# kurskTovideroRaspi.net
KiCad netlist of a schematic drawn in EAGLE
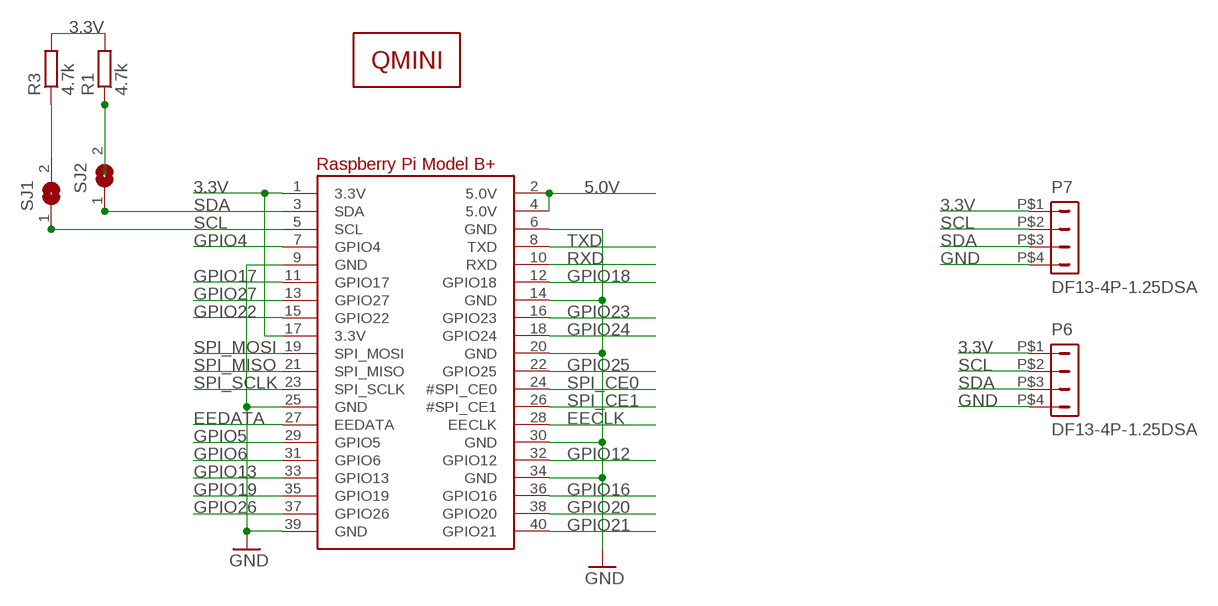
[diagram p0: schematic, sheet 1]
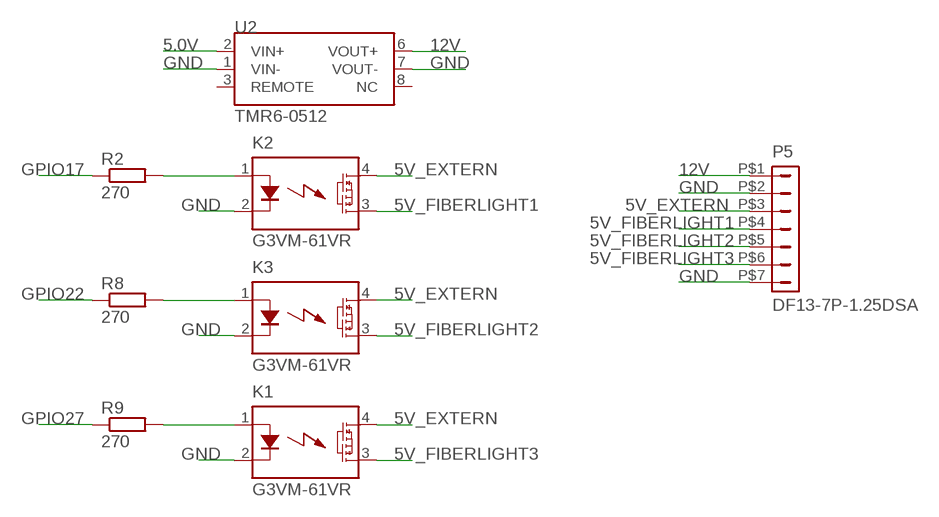
[diagram p1: schematic, sheet 2]
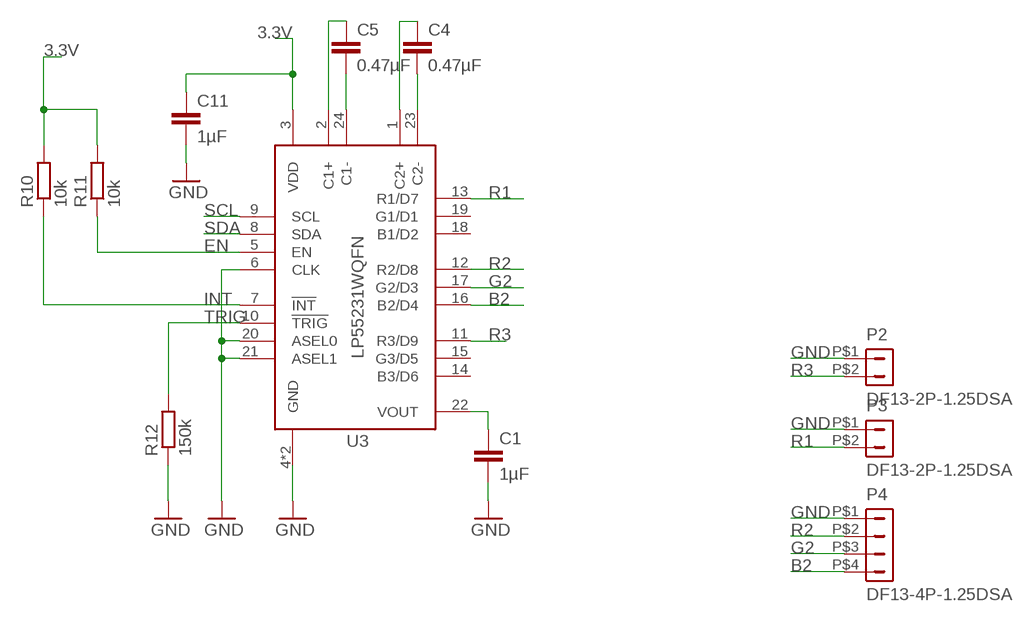
[diagram p2: schematic, sheet 3]
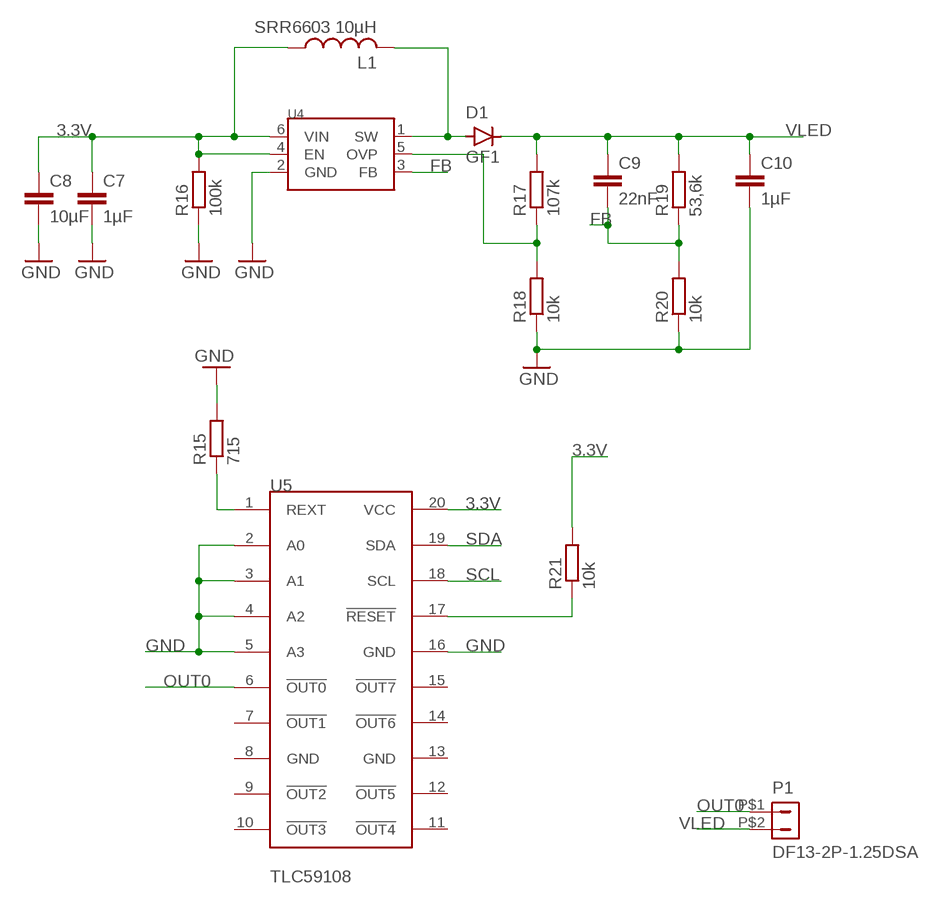
[diagram p3: schematic, sheet 4]

(export (version "E")
  (design (tool "Eeschema 10.0.6"))
  (components
    (comp (ref "K1")
      (value "G3VM-61VR")
      (footprint "eagle-import:SOP04")
      (description "NO DESCRIPTION")
      (fields
        (field (name "MANUFACTURER") "UNKNOWN MANUFACTURER")
        (field (name "MANUFACTURERPARTNUMBER") "UNKNOWN MANUFACTURER PART NUMBER")
        (field (name "MF") "OMRON")
        (field (name "MPN") "G3VM-61VR(TR05)")
        (field (name "OC_FARNELL") "2889501")
      )
      (libsource (lib "eagle-import") (part "AQYSOP22"))
    )
    (comp (ref "K2")
      (value "G3VM-61VR")
      (footprint "eagle-import:SOP04")
      (description "NO DESCRIPTION")
      (fields
        (field (name "MANUFACTURER") "UNKNOWN MANUFACTURER")
        (field (name "MANUFACTURERPARTNUMBER") "UNKNOWN MANUFACTURER PART NUMBER")
        (field (name "MF") "OMRON")
        (field (name "MPN") "G3VM-61VR(TR05)")
        (field (name "OC_FARNELL") "2889501")
      )
      (libsource (lib "eagle-import") (part "AQYSOP22"))
    )
    (comp (ref "K3")
      (value "G3VM-61VR")
      (footprint "eagle-import:SOP04")
      (description "NO DESCRIPTION")
      (fields
        (field (name "MANUFACTURER") "UNKNOWN MANUFACTURER")
        (field (name "MANUFACTURERPARTNUMBER") "UNKNOWN MANUFACTURER PART NUMBER")
        (field (name "MF") "OMRON")
        (field (name "MPN") "G3VM-61VR(TR05)")
        (field (name "OC_FARNELL") "2889501")
      )
      (libsource (lib "eagle-import") (part "AQYSOP22"))
    )
    (comp (ref "P5")
      (value "DF13-7P-1.25DSA")
      (footprint "eagle-import:DF13-7P-1.25DSA")
      (description "NO DESCRIPTION")
      (fields
        (field (name "MANUFACTURER") "UNKNOWN MANUFACTURER")
        (field (name "MANUFACTURERPARTNUMBER") "UNKNOWN MANUFACTURER PART NUMBER")
      )
      (libsource (lib "eagle-import") (part "DF13-7P-1.25DSA"))
    )
    (comp (ref "R2")
      (value "270")
      (footprint "eagle-import:R0805")
      (description "NO DESCRIPTION")
      (fields
        (field (name "MANUFACTURER") "UNKNOWN MANUFACTURER")
        (field (name "MANUFACTURERPARTNUMBER") "UNKNOWN MANUFACTURER PART NUMBER")
      )
      (libsource (lib "eagle-import") (part "R-EU_R0805"))
    )
    (comp (ref "R8")
      (value "270")
      (footprint "eagle-import:R0805")
      (description "NO DESCRIPTION")
      (fields
        (field (name "MANUFACTURER") "UNKNOWN MANUFACTURER")
        (field (name "MANUFACTURERPARTNUMBER") "UNKNOWN MANUFACTURER PART NUMBER")
      )
      (libsource (lib "eagle-import") (part "R-EU_R0805"))
    )
    (comp (ref "R9")
      (value "270")
      (footprint "eagle-import:R0805")
      (description "NO DESCRIPTION")
      (fields
        (field (name "MANUFACTURER") "UNKNOWN MANUFACTURER")
        (field (name "MANUFACTURERPARTNUMBER") "UNKNOWN MANUFACTURER PART NUMBER")
      )
      (libsource (lib "eagle-import") (part "R-EU_R0805"))
    )
    (comp (ref "U2")
      (value "TMR6-0512")
      (footprint "eagle-import:TMR6-0512")
      (description "NO DESCRIPTION")
      (fields
        (field (name "MANUFACTURER") "UNKNOWN MANUFACTURER")
        (field (name "MANUFACTURERPARTNUMBER") "UNKNOWN MANUFACTURER PART NUMBER")
      )
      (libsource (lib "eagle-import") (part "TMR6-0512"))
    )
    (comp (ref "C1")
      (value "1µF")
      (footprint "eagle-import:C0805")
      (description "NO DESCRIPTION")
      (fields
        (field (name "MANUFACTURER") "UNKNOWN MANUFACTURER")
        (field (name "MANUFACTURERPARTNUMBER") "UNKNOWN MANUFACTURER PART NUMBER")
      )
      (libsource (lib "eagle-import") (part "C-EUC0805"))
    )
    (comp (ref "C4")
      (value "0.47µF")
      (footprint "eagle-import:C0805")
      (description "NO DESCRIPTION")
      (fields
        (field (name "MANUFACTURER") "UNKNOWN MANUFACTURER")
        (field (name "MANUFACTURERPARTNUMBER") "UNKNOWN MANUFACTURER PART NUMBER")
      )
      (libsource (lib "eagle-import") (part "C-EUC0805"))
    )
    (comp (ref "C5")
      (value "0.47µF")
      (footprint "eagle-import:C0805")
      (description "NO DESCRIPTION")
      (fields
        (field (name "MANUFACTURER") "UNKNOWN MANUFACTURER")
        (field (name "MANUFACTURERPARTNUMBER") "UNKNOWN MANUFACTURER PART NUMBER")
      )
      (libsource (lib "eagle-import") (part "C-EUC0805"))
    )
    (comp (ref "C11")
      (value "1µF")
      (footprint "eagle-import:C0805")
      (description "NO DESCRIPTION")
      (fields
        (field (name "MANUFACTURER") "UNKNOWN MANUFACTURER")
        (field (name "MANUFACTURERPARTNUMBER") "UNKNOWN MANUFACTURER PART NUMBER")
      )
      (libsource (lib "eagle-import") (part "C-EUC0805"))
    )
    (comp (ref "P2")
      (value "DF13-2P-1.25DSA")
      (footprint "eagle-import:DF13-2P-1.25DSA")
      (description "NO DESCRIPTION")
      (fields
        (field (name "MANUFACTURER") "UNKNOWN MANUFACTURER")
        (field (name "MANUFACTURERPARTNUMBER") "UNKNOWN MANUFACTURER PART NUMBER")
      )
      (libsource (lib "eagle-import") (part "DF13-2P-1.25DSA"))
    )
    (comp (ref "P3")
      (value "DF13-2P-1.25DSA")
      (footprint "eagle-import:DF13-2P-1.25DSA")
      (description "NO DESCRIPTION")
      (fields
        (field (name "MANUFACTURER") "UNKNOWN MANUFACTURER")
        (field (name "MANUFACTURERPARTNUMBER") "UNKNOWN MANUFACTURER PART NUMBER")
      )
      (libsource (lib "eagle-import") (part "DF13-2P-1.25DSA"))
    )
    (comp (ref "P4")
      (value "DF13-4P-1.25DSA")
      (footprint "eagle-import:DF13-4P-1.25DSA")
      (description "NO DESCRIPTION")
      (fields
        (field (name "MANUFACTURER") "UNKNOWN MANUFACTURER")
        (field (name "MANUFACTURERPARTNUMBER") "UNKNOWN MANUFACTURER PART NUMBER")
      )
      (libsource (lib "eagle-import") (part "DF13-4P-1.25DSA"))
    )
    (comp (ref "R10")
      (value "10k")
      (footprint "eagle-import:R0805")
      (description "NO DESCRIPTION")
      (fields
        (field (name "MANUFACTURER") "UNKNOWN MANUFACTURER")
        (field (name "MANUFACTURERPARTNUMBER") "UNKNOWN MANUFACTURER PART NUMBER")
      )
      (libsource (lib "eagle-import") (part "R-EU_R0805"))
    )
    (comp (ref "R11")
      (value "10k")
      (footprint "eagle-import:R0805")
      (description "NO DESCRIPTION")
      (fields
        (field (name "MANUFACTURER") "UNKNOWN MANUFACTURER")
        (field (name "MANUFACTURERPARTNUMBER") "UNKNOWN MANUFACTURER PART NUMBER")
      )
      (libsource (lib "eagle-import") (part "R-EU_R0805"))
    )
    (comp (ref "R12")
      (value "150k")
      (footprint "eagle-import:R0805")
      (description "NO DESCRIPTION")
      (fields
        (field (name "MANUFACTURER") "UNKNOWN MANUFACTURER")
        (field (name "MANUFACTURERPARTNUMBER") "UNKNOWN MANUFACTURER PART NUMBER")
      )
      (libsource (lib "eagle-import") (part "R-EU_R0805"))
    )
    (comp (ref "U3")
      (value "LP55231WQFN")
      (footprint "eagle-import:WQFN-24")
      (description "NO DESCRIPTION")
      (fields
        (field (name "MANUFACTURER") "UNKNOWN MANUFACTURER")
        (field (name "MANUFACTURERPARTNUMBER") "UNKNOWN MANUFACTURER PART NUMBER")
      )
      (libsource (lib "eagle-import") (part "LP55231WQFN"))
    )
    (comp (ref "P6")
      (value "DF13-4P-1.25DSA")
      (footprint "eagle-import:DF13-4P-1.25DSA")
      (description "NO DESCRIPTION")
      (fields
        (field (name "MANUFACTURER") "UNKNOWN MANUFACTURER")
        (field (name "MANUFACTURERPARTNUMBER") "UNKNOWN MANUFACTURER PART NUMBER")
      )
      (libsource (lib "eagle-import") (part "DF13-4P-1.25DSA"))
    )
    (comp (ref "P7")
      (value "DF13-4P-1.25DSA")
      (footprint "eagle-import:DF13-4P-1.25DSA")
      (description "NO DESCRIPTION")
      (fields
        (field (name "MANUFACTURER") "UNKNOWN MANUFACTURER")
        (field (name "MANUFACTURERPARTNUMBER") "UNKNOWN MANUFACTURER PART NUMBER")
      )
      (libsource (lib "eagle-import") (part "DF13-4P-1.25DSA"))
    )
    (comp (ref "R1")
      (value "4.7k")
      (footprint "eagle-import:R0805")
      (description "NO DESCRIPTION")
      (fields
        (field (name "MANUFACTURER") "UNKNOWN MANUFACTURER")
        (field (name "MANUFACTURERPARTNUMBER") "UNKNOWN MANUFACTURER PART NUMBER")
      )
      (libsource (lib "eagle-import") (part "R-EU_R0805"))
    )
    (comp (ref "R3")
      (value "4.7k")
      (footprint "eagle-import:R0805")
      (description "NO DESCRIPTION")
      (fields
        (field (name "MANUFACTURER") "UNKNOWN MANUFACTURER")
        (field (name "MANUFACTURERPARTNUMBER") "UNKNOWN MANUFACTURER PART NUMBER")
      )
      (libsource (lib "eagle-import") (part "R-EU_R0805"))
    )
    (comp (ref "RPI1")
      (value "RASPBERRYPI_BPLUS_HATNOSLOTS")
      (footprint "eagle-import:PI_HAT_NOSLOTS")
      (description "NO DESCRIPTION")
      (fields
        (field (name "MANUFACTURER") "UNKNOWN MANUFACTURER")
        (field (name "MANUFACTURERPARTNUMBER") "UNKNOWN MANUFACTURER PART NUMBER")
      )
      (libsource (lib "eagle-import") (part "RASPBERRYPI_BPLUS_HATNOSLOTS"))
    )
    (comp (ref "SJ1") (value "SJ") (footprint "eagle-import:SJ") (libsource (lib "eagle-import") (part "SJ")))
    (comp (ref "SJ2") (value "SJ") (footprint "eagle-import:SJ") (libsource (lib "eagle-import") (part "SJ")))
    (comp (ref "U$1")
      (value "QMINI")
      (footprint "eagle-import:QMINI")
      (description "NO DESCRIPTION")
      (fields
        (field (name "MANUFACTURER") "UNKNOWN MANUFACTURER")
        (field (name "MANUFACTURERPARTNUMBER") "UNKNOWN MANUFACTURER PART NUMBER")
      )
      (libsource (lib "eagle-import") (part "QMINI"))
    )
    (comp (ref "C7")
      (value "1µF")
      (footprint "eagle-import:C0805")
      (description "NO DESCRIPTION")
      (fields
        (field (name "MANUFACTURER") "UNKNOWN MANUFACTURER")
        (field (name "MANUFACTURERPARTNUMBER") "UNKNOWN MANUFACTURER PART NUMBER")
      )
      (libsource (lib "eagle-import") (part "C-EUC0805"))
    )
    (comp (ref "C8")
      (value "10µF")
      (footprint "eagle-import:C0805")
      (description "NO DESCRIPTION")
      (fields
        (field (name "MANUFACTURER") "UNKNOWN MANUFACTURER")
        (field (name "MANUFACTURERPARTNUMBER") "UNKNOWN MANUFACTURER PART NUMBER")
      )
      (libsource (lib "eagle-import") (part "C-EUC0805"))
    )
    (comp (ref "C9")
      (value "22nF")
      (footprint "eagle-import:C0805")
      (description "NO DESCRIPTION")
      (fields
        (field (name "MANUFACTURER") "UNKNOWN MANUFACTURER")
        (field (name "MANUFACTURERPARTNUMBER") "UNKNOWN MANUFACTURER PART NUMBER")
      )
      (libsource (lib "eagle-import") (part "C-EUC0805"))
    )
    (comp (ref "C10")
      (value "1µF")
      (footprint "eagle-import:C0805")
      (description "NO DESCRIPTION")
      (fields
        (field (name "MANUFACTURER") "UNKNOWN MANUFACTURER")
        (field (name "MANUFACTURERPARTNUMBER") "UNKNOWN MANUFACTURER PART NUMBER")
      )
      (libsource (lib "eagle-import") (part "C-EUC0805"))
    )
    (comp (ref "D1")
      (value "GF1")
      (footprint "eagle-import:SMA-DO214AC")
      (description "NO DESCRIPTION")
      (fields
        (field (name "MANUFACTURER") "UNKNOWN MANUFACTURER")
        (field (name "MANUFACTURERPARTNUMBER") "UNKNOWN MANUFACTURER PART NUMBER")
      )
      (libsource (lib "eagle-import") (part "GF1"))
    )
    (comp (ref "L1")
      (value "SRR6603 10µH")
      (footprint "eagle-import:SRR6603")
      (description "NO DESCRIPTION")
      (fields
        (field (name "MANUFACTURER") "UNKNOWN MANUFACTURER")
        (field (name "MANUFACTURERPARTNUMBER") "UNKNOWN MANUFACTURER PART NUMBER")
      )
      (libsource (lib "eagle-import") (part "SRR6603"))
    )
    (comp (ref "P1")
      (value "DF13-2P-1.25DSA")
      (footprint "eagle-import:DF13-2P-1.25DSA")
      (description "NO DESCRIPTION")
      (fields
        (field (name "MANUFACTURER") "UNKNOWN MANUFACTURER")
        (field (name "MANUFACTURERPARTNUMBER") "UNKNOWN MANUFACTURER PART NUMBER")
      )
      (libsource (lib "eagle-import") (part "DF13-2P-1.25DSA"))
    )
    (comp (ref "R15")
      (value "715")
      (footprint "eagle-import:R0805")
      (description "NO DESCRIPTION")
      (fields
        (field (name "MANUFACTURER") "UNKNOWN MANUFACTURER")
        (field (name "MANUFACTURERPARTNUMBER") "UNKNOWN MANUFACTURER PART NUMBER")
      )
      (libsource (lib "eagle-import") (part "R-EU_R0805"))
    )
    (comp (ref "R16")
      (value "100k")
      (footprint "eagle-import:R0805")
      (description "NO DESCRIPTION")
      (fields
        (field (name "MANUFACTURER") "UNKNOWN MANUFACTURER")
        (field (name "MANUFACTURERPARTNUMBER") "UNKNOWN MANUFACTURER PART NUMBER")
      )
      (libsource (lib "eagle-import") (part "R-EU_R0805"))
    )
    (comp (ref "R17")
      (value "107k")
      (footprint "eagle-import:R0805")
      (description "NO DESCRIPTION")
      (fields
        (field (name "MANUFACTURER") "UNKNOWN MANUFACTURER")
        (field (name "MANUFACTURERPARTNUMBER") "UNKNOWN MANUFACTURER PART NUMBER")
      )
      (libsource (lib "eagle-import") (part "R-EU_R0805"))
    )
    (comp (ref "R18")
      (value "10k")
      (footprint "eagle-import:R0805")
      (description "NO DESCRIPTION")
      (fields
        (field (name "MANUFACTURER") "UNKNOWN MANUFACTURER")
        (field (name "MANUFACTURERPARTNUMBER") "UNKNOWN MANUFACTURER PART NUMBER")
      )
      (libsource (lib "eagle-import") (part "R-EU_R0805"))
    )
    (comp (ref "R19")
      (value "53,6k")
      (footprint "eagle-import:R0805")
      (description "NO DESCRIPTION")
      (fields
        (field (name "MANUFACTURER") "UNKNOWN MANUFACTURER")
        (field (name "MANUFACTURERPARTNUMBER") "UNKNOWN MANUFACTURER PART NUMBER")
      )
      (libsource (lib "eagle-import") (part "R-EU_R0805"))
    )
    (comp (ref "R20")
      (value "10k")
      (footprint "eagle-import:R0805")
      (description "NO DESCRIPTION")
      (fields
        (field (name "MANUFACTURER") "UNKNOWN MANUFACTURER")
        (field (name "MANUFACTURERPARTNUMBER") "UNKNOWN MANUFACTURER PART NUMBER")
      )
      (libsource (lib "eagle-import") (part "R-EU_R0805"))
    )
    (comp (ref "R21")
      (value "10k")
      (footprint "eagle-import:R0805")
      (description "NO DESCRIPTION")
      (fields
        (field (name "MANUFACTURER") "UNKNOWN MANUFACTURER")
        (field (name "MANUFACTURERPARTNUMBER") "UNKNOWN MANUFACTURER PART NUMBER")
      )
      (libsource (lib "eagle-import") (part "R-EU_R0805"))
    )
    (comp (ref "U4")
      (value "MIC2619")
      (footprint "eagle-import:SOT-23-6")
      (description "NO DESCRIPTION")
      (fields
        (field (name "MANUFACTURER") "UNKNOWN MANUFACTURER")
        (field (name "MANUFACTURERPARTNUMBER") "UNKNOWN MANUFACTURER PART NUMBER")
      )
      (libsource (lib "eagle-import") (part "MIC2619"))
    )
    (comp (ref "U5")
      (value "TLC59108")
      (footprint "eagle-import:TSSOP20")
      (description "NO DESCRIPTION")
      (fields
        (field (name "MANUFACTURER") "UNKNOWN MANUFACTURER")
        (field (name "MANUFACTURERPARTNUMBER") "UNKNOWN MANUFACTURER PART NUMBER")
      )
      (libsource (lib "eagle-import") (part "TLC59108"))
    )
  )
  (nets
    (net (code "1") (name "3.3V") (class "Default")
      (node (ref "C11") (pin "1") (pinfunction "1_1") (pintype "passive"))
      (node (ref "C7") (pin "1") (pinfunction "1_1") (pintype "passive"))
      (node (ref "C8") (pin "1") (pinfunction "1_1") (pintype "passive"))
      (node (ref "L1") (pin "1") (pinfunction "1_1") (pintype "passive"))
      (node (ref "P6") (pin "P$1") (pinfunction "1_P$1") (pintype "passive"))
      (node (ref "P7") (pin "P$1") (pinfunction "1_P$1") (pintype "passive"))
      (node (ref "R1") (pin "2") (pinfunction "2_2") (pintype "passive"))
      (node (ref "R10") (pin "2") (pinfunction "2_2") (pintype "passive"))
      (node (ref "R11") (pin "2") (pinfunction "2_2") (pintype "passive"))
      (node (ref "R16") (pin "2") (pinfunction "2_2") (pintype "passive"))
      (node (ref "R21") (pin "2") (pinfunction "2_2") (pintype "passive"))
      (node (ref "R3") (pin "2") (pinfunction "2_2") (pintype "passive"))
      (node (ref "RPI1") (pin "1") (pinfunction "3.3V_1") (pintype "power_in"))
      (node (ref "RPI1") (pin "17") (pinfunction "3.3V_17") (pintype "power_in"))
      (node (ref "U3") (pin "3") (pinfunction "VDD_3") (pintype "bidirectional"))
      (node (ref "U4") (pin "4") (pinfunction "EN_4") (pintype "bidirectional"))
      (node (ref "U4") (pin "6") (pinfunction "VIN_6") (pintype "bidirectional"))
      (node (ref "U5") (pin "20") (pinfunction "VCC_20") (pintype "bidirectional"))
    )
    (net (code "2") (name "5.0V") (class "Default")
      (node (ref "RPI1") (pin "2") (pinfunction "5.0V_2") (pintype "power_in"))
      (node (ref "RPI1") (pin "4") (pinfunction "5.0V_4") (pintype "power_in"))
      (node (ref "U2") (pin "2") (pinfunction "VIN+_2") (pintype "bidirectional"))
    )
    (net (code "3") (name "5V_EXTERN") (class "Default")
      (node (ref "K1") (pin "4") (pinfunction "DS1_4") (pintype "passive"))
      (node (ref "K2") (pin "4") (pinfunction "DS1_4") (pintype "passive"))
      (node (ref "K3") (pin "4") (pinfunction "DS1_4") (pintype "passive"))
      (node (ref "P5") (pin "P$3") (pinfunction "3_P$3") (pintype "passive"))
    )
    (net (code "4") (name "5V_FIBERLIGHT1") (class "Default")
      (node (ref "K2") (pin "3") (pinfunction "DS2_3") (pintype "passive"))
      (node (ref "P5") (pin "P$4") (pinfunction "4_P$4") (pintype "passive"))
    )
    (net (code "5") (name "5V_FIBERLIGHT2") (class "Default")
      (node (ref "K3") (pin "3") (pinfunction "DS2_3") (pintype "passive"))
      (node (ref "P5") (pin "P$5") (pinfunction "5_P$5") (pintype "passive"))
    )
    (net (code "6") (name "5V_FIBERLIGHT3") (class "Default")
      (node (ref "K1") (pin "3") (pinfunction "DS2_3") (pintype "passive"))
      (node (ref "P5") (pin "P$6") (pinfunction "6_P$6") (pintype "passive"))
    )
    (net (code "7") (name "12V") (class "Default")
      (node (ref "P5") (pin "P$1") (pinfunction "1_P$1") (pintype "passive"))
      (node (ref "U2") (pin "6") (pinfunction "VOUT+_6") (pintype "bidirectional"))
    )
    (net (code "8") (name "B2") (class "Default")
      (node (ref "P4") (pin "P$4") (pinfunction "4_P$4") (pintype "passive"))
      (node (ref "U3") (pin "16") (pinfunction "B2/D4_16") (pintype "bidirectional"))
    )
    (net (code "9") (name "EECLK") (class "Default")
      (node (ref "RPI1") (pin "28") (pinfunction "EECLK_28") (pintype "power_in"))
    )
    (net (code "10") (name "EEDATA") (class "Default")
      (node (ref "RPI1") (pin "27") (pinfunction "EEDATA_27") (pintype "bidirectional"))
    )
    (net (code "11") (name "EN") (class "Default")
      (node (ref "R11") (pin "1") (pinfunction "1_1") (pintype "passive"))
      (node (ref "U3") (pin "5") (pinfunction "EN_5") (pintype "bidirectional"))
    )
    (net (code "12") (name "FB") (class "Default")
      (node (ref "C9") (pin "2") (pinfunction "2_2") (pintype "passive"))
      (node (ref "R19") (pin "1") (pinfunction "1_1") (pintype "passive"))
      (node (ref "R20") (pin "2") (pinfunction "2_2") (pintype "passive"))
      (node (ref "U4") (pin "3") (pinfunction "FB_3") (pintype "bidirectional"))
    )
    (net (code "13") (name "G2") (class "Default")
      (node (ref "P4") (pin "P$3") (pinfunction "3_P$3") (pintype "passive"))
      (node (ref "U3") (pin "17") (pinfunction "G2/D3_17") (pintype "bidirectional"))
    )
    (net (code "14") (name "GND") (class "Default")
      (node (ref "C1") (pin "2") (pinfunction "2_2") (pintype "passive"))
      (node (ref "C10") (pin "2") (pinfunction "2_2") (pintype "passive"))
      (node (ref "C11") (pin "2") (pinfunction "2_2") (pintype "passive"))
      (node (ref "C7") (pin "2") (pinfunction "2_2") (pintype "passive"))
      (node (ref "C8") (pin "2") (pinfunction "2_2") (pintype "passive"))
      (node (ref "K1") (pin "2") (pinfunction "K_2") (pintype "passive"))
      (node (ref "K2") (pin "2") (pinfunction "K_2") (pintype "passive"))
      (node (ref "K3") (pin "2") (pinfunction "K_2") (pintype "passive"))
      (node (ref "P2") (pin "P$1") (pinfunction "1_P$1") (pintype "passive"))
      (node (ref "P3") (pin "P$1") (pinfunction "1_P$1") (pintype "passive"))
      (node (ref "P4") (pin "P$1") (pinfunction "1_P$1") (pintype "passive"))
      (node (ref "P5") (pin "P$2") (pinfunction "2_P$2") (pintype "passive"))
      (node (ref "P5") (pin "P$7") (pinfunction "7_P$7") (pintype "passive"))
      (node (ref "P6") (pin "P$4") (pinfunction "4_P$4") (pintype "passive"))
      (node (ref "P7") (pin "P$4") (pinfunction "4_P$4") (pintype "passive"))
      (node (ref "R12") (pin "1") (pinfunction "1_1") (pintype "passive"))
      (node (ref "R15") (pin "2") (pinfunction "2_2") (pintype "passive"))
      (node (ref "R16") (pin "1") (pinfunction "1_1") (pintype "passive"))
      (node (ref "R18") (pin "1") (pinfunction "1_1") (pintype "passive"))
      (node (ref "R20") (pin "1") (pinfunction "1_1") (pintype "passive"))
      (node (ref "RPI1") (pin "14") (pinfunction "GND_14") (pintype "power_in"))
      (node (ref "RPI1") (pin "20") (pinfunction "GND_20") (pintype "power_in"))
      (node (ref "RPI1") (pin "25") (pinfunction "GND_25") (pintype "power_in"))
      (node (ref "RPI1") (pin "30") (pinfunction "GND_30") (pintype "bidirectional"))
      (node (ref "RPI1") (pin "34") (pinfunction "GND_34") (pintype "bidirectional"))
      (node (ref "RPI1") (pin "39") (pinfunction "GND_39") (pintype "power_in"))
      (node (ref "RPI1") (pin "6") (pinfunction "GND_6") (pintype "power_in"))
      (node (ref "RPI1") (pin "9") (pinfunction "GND_9") (pintype "power_in"))
      (node (ref "U2") (pin "1") (pinfunction "VIN-_1") (pintype "bidirectional"))
      (node (ref "U2") (pin "7") (pinfunction "VOUT-_7") (pintype "bidirectional"))
      (node (ref "U3") (pin "20") (pinfunction "ASEL0_20") (pintype "bidirectional"))
      (node (ref "U3") (pin "21") (pinfunction "ASEL1_21") (pintype "bidirectional"))
      (node (ref "U3") (pin "4") (pinfunction "GND_4") (pintype "bidirectional"))
      (node (ref "U3") (pin "6") (pinfunction "CLK_6") (pintype "bidirectional"))
      (node (ref "U3") (pin "EP") (pinfunction "GND_EP") (pintype "bidirectional"))
      (node (ref "U4") (pin "2") (pinfunction "GND_2") (pintype "bidirectional"))
      (node (ref "U5") (pin "16") (pinfunction "GND_16") (pintype "bidirectional"))
      (node (ref "U5") (pin "2") (pinfunction "A0_2") (pintype "bidirectional"))
      (node (ref "U5") (pin "3") (pinfunction "A1_3") (pintype "bidirectional"))
      (node (ref "U5") (pin "4") (pinfunction "A2_4") (pintype "bidirectional"))
      (node (ref "U5") (pin "5") (pinfunction "A3_5") (pintype "bidirectional"))
    )
    (net (code "15") (name "GPIO4") (class "Default")
      (node (ref "RPI1") (pin "7") (pinfunction "GPIO4_7") (pintype "bidirectional"))
    )
    (net (code "16") (name "GPIO5") (class "Default")
      (node (ref "RPI1") (pin "29") (pinfunction "GPIO5_29") (pintype "bidirectional"))
    )
    (net (code "17") (name "GPIO6") (class "Default")
      (node (ref "RPI1") (pin "31") (pinfunction "GPIO6_31") (pintype "power_in"))
    )
    (net (code "18") (name "GPIO12") (class "Default")
      (node (ref "RPI1") (pin "32") (pinfunction "GPIO12_32") (pintype "bidirectional"))
    )
    (net (code "19") (name "GPIO13") (class "Default")
      (node (ref "RPI1") (pin "33") (pinfunction "GPIO13_33") (pintype "bidirectional"))
    )
    (net (code "20") (name "GPIO16") (class "Default")
      (node (ref "RPI1") (pin "36") (pinfunction "GPIO16_36") (pintype "power_in"))
    )
    (net (code "21") (name "GPIO17") (class "Default")
      (node (ref "R2") (pin "1") (pinfunction "1_1") (pintype "passive"))
      (node (ref "RPI1") (pin "11") (pinfunction "GPIO17_11") (pintype "bidirectional"))
    )
    (net (code "22") (name "GPIO18") (class "Default")
      (node (ref "RPI1") (pin "12") (pinfunction "GPIO18_12") (pintype "bidirectional"))
    )
    (net (code "23") (name "GPIO19") (class "Default")
      (node (ref "RPI1") (pin "35") (pinfunction "GPIO19_35") (pintype "bidirectional"))
    )
    (net (code "24") (name "GPIO20") (class "Default")
      (node (ref "RPI1") (pin "38") (pinfunction "GPIO20_38") (pintype "bidirectional"))
    )
    (net (code "25") (name "GPIO21") (class "Default")
      (node (ref "RPI1") (pin "40") (pinfunction "GPIO21_40") (pintype "bidirectional"))
    )
    (net (code "26") (name "GPIO22") (class "Default")
      (node (ref "R8") (pin "1") (pinfunction "1_1") (pintype "passive"))
      (node (ref "RPI1") (pin "15") (pinfunction "GPIO22_15") (pintype "bidirectional"))
    )
    (net (code "27") (name "GPIO23") (class "Default")
      (node (ref "RPI1") (pin "16") (pinfunction "GPIO23_16") (pintype "bidirectional"))
    )
    (net (code "28") (name "GPIO24") (class "Default")
      (node (ref "RPI1") (pin "18") (pinfunction "GPIO24_18") (pintype "bidirectional"))
    )
    (net (code "29") (name "GPIO25") (class "Default")
      (node (ref "RPI1") (pin "22") (pinfunction "GPIO25_22") (pintype "bidirectional"))
    )
    (net (code "30") (name "GPIO26") (class "Default")
      (node (ref "RPI1") (pin "37") (pinfunction "GPIO26_37") (pintype "bidirectional"))
    )
    (net (code "31") (name "GPIO27") (class "Default")
      (node (ref "R9") (pin "1") (pinfunction "1_1") (pintype "passive"))
      (node (ref "RPI1") (pin "13") (pinfunction "GPIO27_13") (pintype "bidirectional"))
    )
    (net (code "32") (name "INT") (class "Default")
      (node (ref "R10") (pin "1") (pinfunction "1_1") (pintype "passive"))
      (node (ref "U3") (pin "7") (pinfunction "~{INT}_7") (pintype "bidirectional"))
    )
    (net (code "33") (name "Net-(K1-A)") (class "Default")
      (node (ref "K1") (pin "1") (pinfunction "A_1") (pintype "passive"))
      (node (ref "R9") (pin "2") (pinfunction "2_2") (pintype "passive"))
    )
    (net (code "34") (name "Net-(K2-A)") (class "Default")
      (node (ref "K2") (pin "1") (pinfunction "A_1") (pintype "passive"))
      (node (ref "R2") (pin "2") (pinfunction "2_2") (pintype "passive"))
    )
    (net (code "35") (name "Net-(K3-A)") (class "Default")
      (node (ref "K3") (pin "1") (pinfunction "A_1") (pintype "passive"))
      (node (ref "R8") (pin "2") (pinfunction "2_2") (pintype "passive"))
    )
    (net (code "36") (name "Net-(R1-Pad1)") (class "Default")
      (node (ref "R1") (pin "1") (pinfunction "1_1") (pintype "passive"))
      (node (ref "SJ2") (pin "2") (pinfunction "2_2") (pintype "passive"))
    )
    (net (code "37") (name "Net-(R3-Pad1)") (class "Default")
      (node (ref "R3") (pin "1") (pinfunction "1_1") (pintype "passive"))
      (node (ref "SJ1") (pin "2") (pinfunction "2_2") (pintype "passive"))
    )
    (net (code "38") (name "Net-(U3-C1+)") (class "Default")
      (node (ref "C5") (pin "1") (pinfunction "1_1") (pintype "passive"))
      (node (ref "U3") (pin "2") (pinfunction "C1+_2") (pintype "bidirectional"))
    )
    (net (code "39") (name "Net-(U3-C1-)") (class "Default")
      (node (ref "C5") (pin "2") (pinfunction "2_2") (pintype "passive"))
      (node (ref "U3") (pin "24") (pinfunction "C1-_24") (pintype "bidirectional"))
    )
    (net (code "40") (name "Net-(U3-C2+)") (class "Default")
      (node (ref "C4") (pin "1") (pinfunction "1_1") (pintype "passive"))
      (node (ref "U3") (pin "1") (pinfunction "C2+_1") (pintype "bidirectional"))
    )
    (net (code "41") (name "Net-(U3-C2-)") (class "Default")
      (node (ref "C4") (pin "2") (pinfunction "2_2") (pintype "passive"))
      (node (ref "U3") (pin "23") (pinfunction "C2-_23") (pintype "bidirectional"))
    )
    (net (code "42") (name "Net-(U3-VOUT)") (class "Default")
      (node (ref "C1") (pin "1") (pinfunction "1_1") (pintype "passive"))
      (node (ref "U3") (pin "22") (pinfunction "VOUT_22") (pintype "bidirectional"))
    )
    (net (code "43") (name "Net-(U4-OVP)") (class "Default")
      (node (ref "R17") (pin "1") (pinfunction "1_1") (pintype "passive"))
      (node (ref "R18") (pin "2") (pinfunction "2_2") (pintype "passive"))
      (node (ref "U4") (pin "5") (pinfunction "OVP_5") (pintype "bidirectional"))
    )
    (net (code "44") (name "Net-(U4-SW)") (class "Default")
      (node (ref "D1") (pin "A") (pinfunction "A_A") (pintype "passive"))
      (node (ref "L1") (pin "2") (pinfunction "2_2") (pintype "passive"))
      (node (ref "U4") (pin "1") (pinfunction "SW_1") (pintype "bidirectional"))
    )
    (net (code "45") (name "Net-(U5-REXT)") (class "Default")
      (node (ref "R15") (pin "1") (pinfunction "1_1") (pintype "passive"))
      (node (ref "U5") (pin "1") (pinfunction "REXT_1") (pintype "bidirectional"))
    )
    (net (code "46") (name "Net-(U5-~{RESET})") (class "Default")
      (node (ref "R21") (pin "1") (pinfunction "1_1") (pintype "passive"))
      (node (ref "U5") (pin "17") (pinfunction "~{RESET}_17") (pintype "bidirectional"))
    )
    (net (code "47") (name "OUT0") (class "Default")
      (node (ref "P1") (pin "P$1") (pinfunction "1_P$1") (pintype "passive"))
      (node (ref "U5") (pin "6") (pinfunction "~{OUT0}_6") (pintype "bidirectional"))
    )
    (net (code "48") (name "R1") (class "Default")
      (node (ref "P3") (pin "P$2") (pinfunction "2_P$2") (pintype "passive"))
      (node (ref "U3") (pin "13") (pinfunction "R1/D7_13") (pintype "bidirectional"))
    )
    (net (code "49") (name "R2") (class "Default")
      (node (ref "P4") (pin "P$2") (pinfunction "2_P$2") (pintype "passive"))
      (node (ref "U3") (pin "12") (pinfunction "R2/D8_12") (pintype "bidirectional"))
    )
    (net (code "50") (name "R3") (class "Default")
      (node (ref "P2") (pin "P$2") (pinfunction "2_P$2") (pintype "passive"))
      (node (ref "U3") (pin "11") (pinfunction "R3/D9_11") (pintype "bidirectional"))
    )
    (net (code "51") (name "RXD") (class "Default")
      (node (ref "RPI1") (pin "10") (pinfunction "RXD_10") (pintype "bidirectional"))
    )
    (net (code "52") (name "SCL") (class "Default")
      (node (ref "P6") (pin "P$2") (pinfunction "2_P$2") (pintype "passive"))
      (node (ref "P7") (pin "P$2") (pinfunction "2_P$2") (pintype "passive"))
      (node (ref "RPI1") (pin "5") (pinfunction "SCL_5") (pintype "bidirectional"))
      (node (ref "SJ1") (pin "1") (pinfunction "1_1") (pintype "passive"))
      (node (ref "U3") (pin "9") (pinfunction "SCL_9") (pintype "bidirectional"))
      (node (ref "U5") (pin "18") (pinfunction "SCL_18") (pintype "bidirectional"))
    )
    (net (code "53") (name "SDA") (class "Default")
      (node (ref "P6") (pin "P$3") (pinfunction "3_P$3") (pintype "passive"))
      (node (ref "P7") (pin "P$3") (pinfunction "3_P$3") (pintype "passive"))
      (node (ref "RPI1") (pin "3") (pinfunction "SDA_3") (pintype "bidirectional"))
      (node (ref "SJ2") (pin "1") (pinfunction "1_1") (pintype "passive"))
      (node (ref "U3") (pin "8") (pinfunction "SDA_8") (pintype "bidirectional"))
      (node (ref "U5") (pin "19") (pinfunction "SDA_19") (pintype "bidirectional"))
    )
    (net (code "54") (name "SPI_CE0") (class "Default")
      (node (ref "RPI1") (pin "24") (pinfunction "#SPI_CE0_24") (pintype "bidirectional"))
    )
    (net (code "55") (name "SPI_CE1") (class "Default")
      (node (ref "RPI1") (pin "26") (pinfunction "#SPI_CE1_26") (pintype "bidirectional"))
    )
    (net (code "56") (name "SPI_MISO") (class "Default")
      (node (ref "RPI1") (pin "21") (pinfunction "SPI_MISO_21") (pintype "bidirectional"))
    )
    (net (code "57") (name "SPI_MOSI") (class "Default")
      (node (ref "RPI1") (pin "19") (pinfunction "SPI_MOSI_19") (pintype "bidirectional"))
    )
    (net (code "58") (name "SPI_SCLK") (class "Default")
      (node (ref "RPI1") (pin "23") (pinfunction "SPI_SCLK_23") (pintype "bidirectional"))
    )
    (net (code "59") (name "TRIG") (class "Default")
      (node (ref "R12") (pin "2") (pinfunction "2_2") (pintype "passive"))
      (node (ref "U3") (pin "10") (pinfunction "~{TRIG}_10") (pintype "bidirectional"))
    )
    (net (code "60") (name "TXD") (class "Default")
      (node (ref "RPI1") (pin "8") (pinfunction "TXD_8") (pintype "output"))
    )
    (net (code "61") (name "VLED") (class "Default")
      (node (ref "C10") (pin "1") (pinfunction "1_1") (pintype "passive"))
      (node (ref "C9") (pin "1") (pinfunction "1_1") (pintype "passive"))
      (node (ref "D1") (pin "K") (pinfunction "C_K") (pintype "passive"))
      (node (ref "P1") (pin "P$2") (pinfunction "2_P$2") (pintype "passive"))
      (node (ref "R17") (pin "2") (pinfunction "2_2") (pintype "passive"))
      (node (ref "R19") (pin "2") (pinfunction "2_2") (pintype "passive"))
    )
    (net (code "62") (name "unconnected-(U2-NC-Pad8)") (class "Default")
      (node (ref "U2") (pin "8") (pinfunction "NC_8") (pintype "bidirectional"))
    )
    (net (code "63") (name "unconnected-(U2-REMOTE-Pad3)") (class "Default")
      (node (ref "U2") (pin "3") (pinfunction "REMOTE_3") (pintype "bidirectional"))
    )
    (net (code "64") (name "unconnected-(U3-B1{slash}D2-Pad18)") (class "Default")
      (node (ref "U3") (pin "18") (pinfunction "B1/D2_18") (pintype "bidirectional"))
    )
    (net (code "65") (name "unconnected-(U3-B3{slash}D6-Pad14)") (class "Default")
      (node (ref "U3") (pin "14") (pinfunction "B3/D6_14") (pintype "bidirectional"))
    )
    (net (code "66") (name "unconnected-(U3-G1{slash}D1-Pad19)") (class "Default")
      (node (ref "U3") (pin "19") (pinfunction "G1/D1_19") (pintype "bidirectional"))
    )
    (net (code "67") (name "unconnected-(U3-G3{slash}D5-Pad15)") (class "Default")
      (node (ref "U3") (pin "15") (pinfunction "G3/D5_15") (pintype "bidirectional"))
    )
    (net (code "68") (name "unconnected-(U5-GND-Pad8)") (class "Default")
      (node (ref "U5") (pin "8") (pinfunction "GND_8") (pintype "bidirectional"))
    )
    (net (code "69") (name "unconnected-(U5-GND-Pad13)") (class "Default")
      (node (ref "U5") (pin "13") (pinfunction "GND_13") (pintype "bidirectional"))
    )
    (net (code "70") (name "unconnected-(U5-~{OUT1}-Pad7)") (class "Default")
      (node (ref "U5") (pin "7") (pinfunction "~{OUT1}_7") (pintype "bidirectional"))
    )
    (net (code "71") (name "unconnected-(U5-~{OUT2}-Pad9)") (class "Default")
      (node (ref "U5") (pin "9") (pinfunction "~{OUT2}_9") (pintype "bidirectional"))
    )
    (net (code "72") (name "unconnected-(U5-~{OUT3}-Pad10)") (class "Default")
      (node (ref "U5") (pin "10") (pinfunction "~{OUT3}_10") (pintype "bidirectional"))
    )
    (net (code "73") (name "unconnected-(U5-~{OUT4}-Pad11)") (class "Default")
      (node (ref "U5") (pin "11") (pinfunction "~{OUT4}_11") (pintype "bidirectional"))
    )
    (net (code "74") (name "unconnected-(U5-~{OUT5}-Pad12)") (class "Default")
      (node (ref "U5") (pin "12") (pinfunction "~{OUT5}_12") (pintype "bidirectional"))
    )
    (net (code "75") (name "unconnected-(U5-~{OUT6}-Pad14)") (class "Default")
      (node (ref "U5") (pin "14") (pinfunction "~{OUT6}_14") (pintype "bidirectional"))
    )
    (net (code "76") (name "unconnected-(U5-~{OUT7}-Pad15)") (class "Default")
      (node (ref "U5") (pin "15") (pinfunction "~{OUT7}_15") (pintype "bidirectional"))
    )
  )
)
